# uTCA_Tongue3.net
KiCad netlist of a schematic drawn in Altium Designer
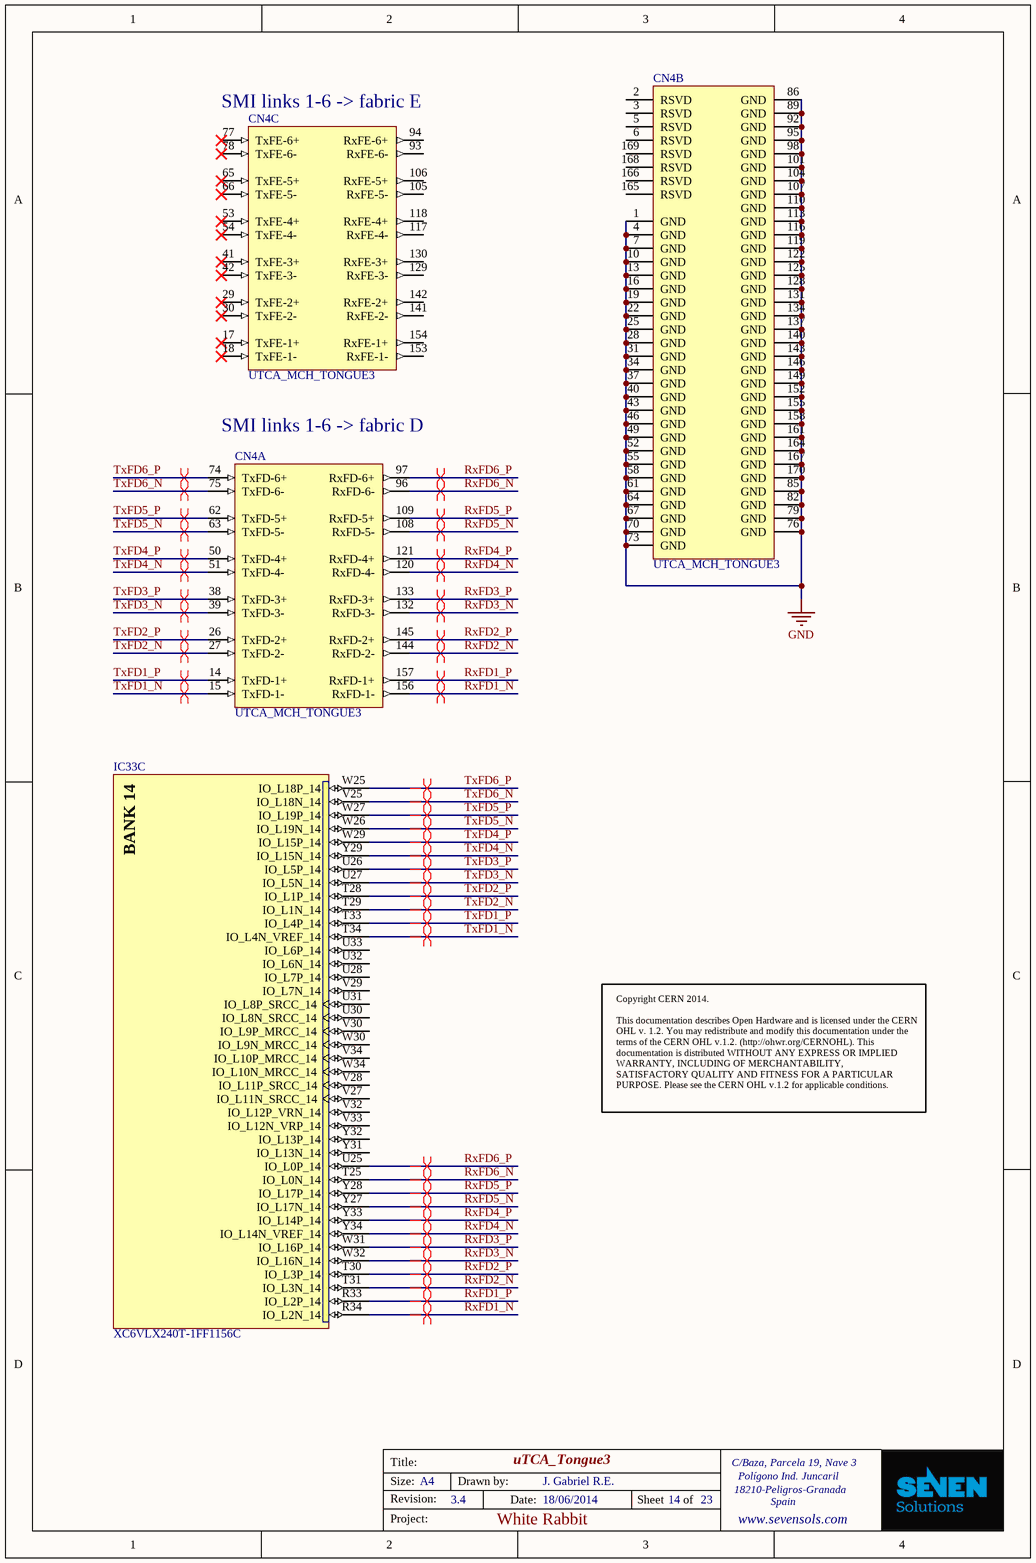
[diagram p0: uTCA_Tongue3.SchDoc]

(export (version "E")
  (design (tool "Eeschema 10.0.6"))
  (components
    (comp (ref "CN4")
      (value "UTCA_MCH_TONGUE3")
      (footprint "UTCA_MCH_TONGUE2_3_4")
      (description "microTCA MTCA.0 standard MCH connector 3")
      (libsource (lib "wr_switch") (part "UTCA_MCH_TONGUE3"))
    )
    (comp (ref "IC33")
      (value "XC6VLX240T-1FF1156C")
      (footprint "FF1156")
      (fields (field (name "PUBLISHER") "Altium Limited"))
      (libsource (lib "Xilinx Virtex-6") (part "XC6VLX240T-1FF1156C"))
    )
  )
  (nets
    (net (code "1") (name "/RxFD1_N") (class "Default")
      (node (ref "CN4") (pin "156") (pinfunction "RxFD-1-_156") (pintype "output"))
      (node (ref "IC33") (pin "R34") (pinfunction "IO_L2N_14_R34") (pintype "bidirectional"))
    )
    (net (code "2") (name "/RxFD1_P") (class "Default")
      (node (ref "CN4") (pin "157") (pinfunction "RxFD-1+_157") (pintype "output"))
      (node (ref "IC33") (pin "R33") (pinfunction "IO_L2P_14_R33") (pintype "bidirectional"))
    )
    (net (code "3") (name "/RxFD2_N") (class "Default")
      (node (ref "CN4") (pin "144") (pinfunction "RxFD-2-_144") (pintype "output"))
      (node (ref "IC33") (pin "T31") (pinfunction "IO_L3N_14_T31") (pintype "bidirectional"))
    )
    (net (code "4") (name "/RxFD2_P") (class "Default")
      (node (ref "CN4") (pin "145") (pinfunction "RxFD-2+_145") (pintype "output"))
      (node (ref "IC33") (pin "T30") (pinfunction "IO_L3P_14_T30") (pintype "bidirectional"))
    )
    (net (code "5") (name "/RxFD3_N") (class "Default")
      (node (ref "CN4") (pin "132") (pinfunction "RxFD-3-_132") (pintype "output"))
      (node (ref "IC33") (pin "W32") (pinfunction "IO_L16N_14_W32") (pintype "bidirectional"))
    )
    (net (code "6") (name "/RxFD3_P") (class "Default")
      (node (ref "CN4") (pin "133") (pinfunction "RxFD-3+_133") (pintype "output"))
      (node (ref "IC33") (pin "W31") (pinfunction "IO_L16P_14_W31") (pintype "bidirectional"))
    )
    (net (code "7") (name "/RxFD4_N") (class "Default")
      (node (ref "CN4") (pin "120") (pinfunction "RxFD-4-_120") (pintype "output"))
      (node (ref "IC33") (pin "Y34") (pinfunction "IO_L14N_VREF_14_Y34") (pintype "bidirectional"))
    )
    (net (code "8") (name "/RxFD4_P") (class "Default")
      (node (ref "CN4") (pin "121") (pinfunction "RxFD-4+_121") (pintype "output"))
      (node (ref "IC33") (pin "Y33") (pinfunction "IO_L14P_14_Y33") (pintype "bidirectional"))
    )
    (net (code "9") (name "/RxFD5_N") (class "Default")
      (node (ref "CN4") (pin "108") (pinfunction "RxFD-5-_108") (pintype "output"))
      (node (ref "IC33") (pin "Y27") (pinfunction "IO_L17N_14_Y27") (pintype "bidirectional"))
    )
    (net (code "10") (name "/RxFD5_P") (class "Default")
      (node (ref "CN4") (pin "109") (pinfunction "RxFD-5+_109") (pintype "output"))
      (node (ref "IC33") (pin "Y28") (pinfunction "IO_L17P_14_Y28") (pintype "bidirectional"))
    )
    (net (code "11") (name "/RxFD6_N") (class "Default")
      (node (ref "CN4") (pin "96") (pinfunction "RxFD-6-_96") (pintype "output"))
      (node (ref "IC33") (pin "T25") (pinfunction "IO_L0N_14_T25") (pintype "bidirectional"))
    )
    (net (code "12") (name "/RxFD6_P") (class "Default")
      (node (ref "CN4") (pin "97") (pinfunction "RxFD-6+_97") (pintype "output"))
      (node (ref "IC33") (pin "U25") (pinfunction "IO_L0P_14_U25") (pintype "bidirectional"))
    )
    (net (code "13") (name "/TxFD1_N") (class "Default")
      (node (ref "CN4") (pin "15") (pinfunction "TxFD-1-_15") (pintype "input"))
      (node (ref "IC33") (pin "T34") (pinfunction "IO_L4N_VREF_14_T34") (pintype "bidirectional"))
    )
    (net (code "14") (name "/TxFD1_P") (class "Default")
      (node (ref "CN4") (pin "14") (pinfunction "TxFD-1+_14") (pintype "input"))
      (node (ref "IC33") (pin "T33") (pinfunction "IO_L4P_14_T33") (pintype "bidirectional"))
    )
    (net (code "15") (name "/TxFD2_N") (class "Default")
      (node (ref "CN4") (pin "27") (pinfunction "TxFD-2-_27") (pintype "input"))
      (node (ref "IC33") (pin "T29") (pinfunction "IO_L1N_14_T29") (pintype "bidirectional"))
    )
    (net (code "16") (name "/TxFD2_P") (class "Default")
      (node (ref "CN4") (pin "26") (pinfunction "TxFD-2+_26") (pintype "input"))
      (node (ref "IC33") (pin "T28") (pinfunction "IO_L1P_14_T28") (pintype "bidirectional"))
    )
    (net (code "17") (name "/TxFD3_N") (class "Default")
      (node (ref "CN4") (pin "39") (pinfunction "TxFD-3-_39") (pintype "input"))
      (node (ref "IC33") (pin "U27") (pinfunction "IO_L5N_14_U27") (pintype "bidirectional"))
    )
    (net (code "18") (name "/TxFD3_P") (class "Default")
      (node (ref "CN4") (pin "38") (pinfunction "TxFD-3+_38") (pintype "input"))
      (node (ref "IC33") (pin "U26") (pinfunction "IO_L5P_14_U26") (pintype "bidirectional"))
    )
    (net (code "19") (name "/TxFD4_N") (class "Default")
      (node (ref "CN4") (pin "51") (pinfunction "TxFD-4-_51") (pintype "input"))
      (node (ref "IC33") (pin "Y29") (pinfunction "IO_L15N_14_Y29") (pintype "bidirectional"))
    )
    (net (code "20") (name "/TxFD4_P") (class "Default")
      (node (ref "CN4") (pin "50") (pinfunction "TxFD-4+_50") (pintype "input"))
      (node (ref "IC33") (pin "W29") (pinfunction "IO_L15P_14_W29") (pintype "bidirectional"))
    )
    (net (code "21") (name "/TxFD5_N") (class "Default")
      (node (ref "CN4") (pin "63") (pinfunction "TxFD-5-_63") (pintype "input"))
      (node (ref "IC33") (pin "W26") (pinfunction "IO_L19N_14_W26") (pintype "bidirectional"))
    )
    (net (code "22") (name "/TxFD5_P") (class "Default")
      (node (ref "CN4") (pin "62") (pinfunction "TxFD-5+_62") (pintype "input"))
      (node (ref "IC33") (pin "W27") (pinfunction "IO_L19P_14_W27") (pintype "bidirectional"))
    )
    (net (code "23") (name "/TxFD6_N") (class "Default")
      (node (ref "CN4") (pin "75") (pinfunction "TxFD-6-_75") (pintype "input"))
      (node (ref "IC33") (pin "V25") (pinfunction "IO_L18N_14_V25") (pintype "bidirectional"))
    )
    (net (code "24") (name "/TxFD6_P") (class "Default")
      (node (ref "CN4") (pin "74") (pinfunction "TxFD-6+_74") (pintype "input"))
      (node (ref "IC33") (pin "W25") (pinfunction "IO_L18P_14_W25") (pintype "bidirectional"))
    )
    (net (code "25") (name "GND") (class "Default")
      (node (ref "CN4") (pin "1") (pinfunction "GND_1") (pintype "power_in"))
      (node (ref "CN4") (pin "10") (pinfunction "GND_10") (pintype "power_in"))
      (node (ref "CN4") (pin "101") (pinfunction "GND_101") (pintype "power_in"))
      (node (ref "CN4") (pin "104") (pinfunction "GND_104") (pintype "power_in"))
      (node (ref "CN4") (pin "107") (pinfunction "GND_107") (pintype "power_in"))
      (node (ref "CN4") (pin "110") (pinfunction "GND_110") (pintype "power_in"))
      (node (ref "CN4") (pin "113") (pinfunction "GND_113") (pintype "power_in"))
      (node (ref "CN4") (pin "116") (pinfunction "GND_116") (pintype "power_in"))
      (node (ref "CN4") (pin "119") (pinfunction "GND_119") (pintype "power_in"))
      (node (ref "CN4") (pin "122") (pinfunction "GND_122") (pintype "power_in"))
      (node (ref "CN4") (pin "125") (pinfunction "GND_125") (pintype "power_in"))
      (node (ref "CN4") (pin "128") (pinfunction "GND_128") (pintype "power_in"))
      (node (ref "CN4") (pin "13") (pinfunction "GND_13") (pintype "power_in"))
      (node (ref "CN4") (pin "131") (pinfunction "GND_131") (pintype "power_in"))
      (node (ref "CN4") (pin "134") (pinfunction "GND_134") (pintype "power_in"))
      (node (ref "CN4") (pin "137") (pinfunction "GND_137") (pintype "power_in"))
      (node (ref "CN4") (pin "140") (pinfunction "GND_140") (pintype "power_in"))
      (node (ref "CN4") (pin "143") (pinfunction "GND_143") (pintype "power_in"))
      (node (ref "CN4") (pin "146") (pinfunction "GND_146") (pintype "power_in"))
      (node (ref "CN4") (pin "149") (pinfunction "GND_149") (pintype "power_in"))
      (node (ref "CN4") (pin "152") (pinfunction "GND_152") (pintype "power_in"))
      (node (ref "CN4") (pin "155") (pinfunction "GND_155") (pintype "power_in"))
      (node (ref "CN4") (pin "158") (pinfunction "GND_158") (pintype "power_in"))
      (node (ref "CN4") (pin "16") (pinfunction "GND_16") (pintype "power_in"))
      (node (ref "CN4") (pin "161") (pinfunction "GND_161") (pintype "power_in"))
      (node (ref "CN4") (pin "164") (pinfunction "GND_164") (pintype "power_in"))
      (node (ref "CN4") (pin "167") (pinfunction "GND_167") (pintype "power_in"))
      (node (ref "CN4") (pin "170") (pinfunction "GND_170") (pintype "power_in"))
      (node (ref "CN4") (pin "19") (pinfunction "GND_19") (pintype "power_in"))
      (node (ref "CN4") (pin "22") (pinfunction "GND_22") (pintype "power_in"))
      (node (ref "CN4") (pin "25") (pinfunction "GND_25") (pintype "power_in"))
      (node (ref "CN4") (pin "28") (pinfunction "GND_28") (pintype "power_in"))
      (node (ref "CN4") (pin "31") (pinfunction "GND_31") (pintype "power_in"))
      (node (ref "CN4") (pin "34") (pinfunction "GND_34") (pintype "power_in"))
      (node (ref "CN4") (pin "37") (pinfunction "GND_37") (pintype "power_in"))
      (node (ref "CN4") (pin "4") (pinfunction "GND_4") (pintype "power_in"))
      (node (ref "CN4") (pin "40") (pinfunction "GND_40") (pintype "power_in"))
      (node (ref "CN4") (pin "43") (pinfunction "GND_43") (pintype "power_in"))
      (node (ref "CN4") (pin "46") (pinfunction "GND_46") (pintype "power_in"))
      (node (ref "CN4") (pin "49") (pinfunction "GND_49") (pintype "power_in"))
      (node (ref "CN4") (pin "52") (pinfunction "GND_52") (pintype "power_in"))
      (node (ref "CN4") (pin "55") (pinfunction "GND_55") (pintype "power_in"))
      (node (ref "CN4") (pin "58") (pinfunction "GND_58") (pintype "power_in"))
      (node (ref "CN4") (pin "61") (pinfunction "GND_61") (pintype "power_in"))
      (node (ref "CN4") (pin "64") (pinfunction "GND_64") (pintype "power_in"))
      (node (ref "CN4") (pin "67") (pinfunction "GND_67") (pintype "power_in"))
      (node (ref "CN4") (pin "7") (pinfunction "GND_7") (pintype "power_in"))
      (node (ref "CN4") (pin "70") (pinfunction "GND_70") (pintype "power_in"))
      (node (ref "CN4") (pin "73") (pinfunction "GND_73") (pintype "power_in"))
      (node (ref "CN4") (pin "76") (pinfunction "GND_76") (pintype "power_in"))
      (node (ref "CN4") (pin "79") (pinfunction "GND_79") (pintype "power_in"))
      (node (ref "CN4") (pin "82") (pinfunction "GND_82") (pintype "power_in"))
      (node (ref "CN4") (pin "85") (pinfunction "GND_85") (pintype "power_in"))
      (node (ref "CN4") (pin "86") (pinfunction "GND_86") (pintype "power_in"))
      (node (ref "CN4") (pin "89") (pinfunction "GND_89") (pintype "power_in"))
      (node (ref "CN4") (pin "92") (pinfunction "GND_92") (pintype "power_in"))
      (node (ref "CN4") (pin "95") (pinfunction "GND_95") (pintype "power_in"))
      (node (ref "CN4") (pin "98") (pinfunction "GND_98") (pintype "power_in"))
    )
    (net (code "26") (name "unconnected-(CN4B-RSVD-Pad2)") (class "Default")
      (node (ref "CN4") (pin "2") (pinfunction "RSVD_2") (pintype "passive"))
    )
    (net (code "27") (name "unconnected-(CN4B-RSVD-Pad3)") (class "Default")
      (node (ref "CN4") (pin "3") (pinfunction "RSVD_3") (pintype "passive"))
    )
    (net (code "28") (name "unconnected-(CN4B-RSVD-Pad5)") (class "Default")
      (node (ref "CN4") (pin "5") (pinfunction "RSVD_5") (pintype "passive"))
    )
    (net (code "29") (name "unconnected-(CN4B-RSVD-Pad6)") (class "Default")
      (node (ref "CN4") (pin "6") (pinfunction "RSVD_6") (pintype "passive"))
    )
    (net (code "30") (name "unconnected-(CN4B-RSVD-Pad165)") (class "Default")
      (node (ref "CN4") (pin "165") (pinfunction "RSVD_165") (pintype "passive"))
    )
    (net (code "31") (name "unconnected-(CN4B-RSVD-Pad166)") (class "Default")
      (node (ref "CN4") (pin "166") (pinfunction "RSVD_166") (pintype "passive"))
    )
    (net (code "32") (name "unconnected-(CN4B-RSVD-Pad168)") (class "Default")
      (node (ref "CN4") (pin "168") (pinfunction "RSVD_168") (pintype "passive"))
    )
    (net (code "33") (name "unconnected-(CN4B-RSVD-Pad169)") (class "Default")
      (node (ref "CN4") (pin "169") (pinfunction "RSVD_169") (pintype "passive"))
    )
    (net (code "34") (name "unconnected-(CN4C-RxFE-1+-Pad154)") (class "Default")
      (node (ref "CN4") (pin "154") (pinfunction "RxFE-1+_154") (pintype "output"))
    )
    (net (code "35") (name "unconnected-(CN4C-RxFE-1--Pad153)") (class "Default")
      (node (ref "CN4") (pin "153") (pinfunction "RxFE-1-_153") (pintype "output"))
    )
    (net (code "36") (name "unconnected-(CN4C-RxFE-2+-Pad142)") (class "Default")
      (node (ref "CN4") (pin "142") (pinfunction "RxFE-2+_142") (pintype "output"))
    )
    (net (code "37") (name "unconnected-(CN4C-RxFE-2--Pad141)") (class "Default")
      (node (ref "CN4") (pin "141") (pinfunction "RxFE-2-_141") (pintype "output"))
    )
    (net (code "38") (name "unconnected-(CN4C-RxFE-3+-Pad130)") (class "Default")
      (node (ref "CN4") (pin "130") (pinfunction "RxFE-3+_130") (pintype "output"))
    )
    (net (code "39") (name "unconnected-(CN4C-RxFE-3--Pad129)") (class "Default")
      (node (ref "CN4") (pin "129") (pinfunction "RxFE-3-_129") (pintype "output"))
    )
    (net (code "40") (name "unconnected-(CN4C-RxFE-4+-Pad118)") (class "Default")
      (node (ref "CN4") (pin "118") (pinfunction "RxFE-4+_118") (pintype "output"))
    )
    (net (code "41") (name "unconnected-(CN4C-RxFE-4--Pad117)") (class "Default")
      (node (ref "CN4") (pin "117") (pinfunction "RxFE-4-_117") (pintype "output"))
    )
    (net (code "42") (name "unconnected-(CN4C-RxFE-5+-Pad106)") (class "Default")
      (node (ref "CN4") (pin "106") (pinfunction "RxFE-5+_106") (pintype "output"))
    )
    (net (code "43") (name "unconnected-(CN4C-RxFE-5--Pad105)") (class "Default")
      (node (ref "CN4") (pin "105") (pinfunction "RxFE-5-_105") (pintype "output"))
    )
    (net (code "44") (name "unconnected-(CN4C-RxFE-6+-Pad94)") (class "Default")
      (node (ref "CN4") (pin "94") (pinfunction "RxFE-6+_94") (pintype "output"))
    )
    (net (code "45") (name "unconnected-(CN4C-RxFE-6--Pad93)") (class "Default")
      (node (ref "CN4") (pin "93") (pinfunction "RxFE-6-_93") (pintype "output"))
    )
    (net (code "46") (name "unconnected-(CN4C-TxFE-1+-Pad17)") (class "Default")
      (node (ref "CN4") (pin "17") (pinfunction "TxFE-1+_17") (pintype "input+no_connect"))
    )
    (net (code "47") (name "unconnected-(CN4C-TxFE-1--Pad18)") (class "Default")
      (node (ref "CN4") (pin "18") (pinfunction "TxFE-1-_18") (pintype "input+no_connect"))
    )
    (net (code "48") (name "unconnected-(CN4C-TxFE-2+-Pad29)") (class "Default")
      (node (ref "CN4") (pin "29") (pinfunction "TxFE-2+_29") (pintype "input+no_connect"))
    )
    (net (code "49") (name "unconnected-(CN4C-TxFE-2--Pad30)") (class "Default")
      (node (ref "CN4") (pin "30") (pinfunction "TxFE-2-_30") (pintype "input+no_connect"))
    )
    (net (code "50") (name "unconnected-(CN4C-TxFE-3+-Pad41)") (class "Default")
      (node (ref "CN4") (pin "41") (pinfunction "TxFE-3+_41") (pintype "input+no_connect"))
    )
    (net (code "51") (name "unconnected-(CN4C-TxFE-3--Pad42)") (class "Default")
      (node (ref "CN4") (pin "42") (pinfunction "TxFE-3-_42") (pintype "input+no_connect"))
    )
    (net (code "52") (name "unconnected-(CN4C-TxFE-4+-Pad53)") (class "Default")
      (node (ref "CN4") (pin "53") (pinfunction "TxFE-4+_53") (pintype "input+no_connect"))
    )
    (net (code "53") (name "unconnected-(CN4C-TxFE-4--Pad54)") (class "Default")
      (node (ref "CN4") (pin "54") (pinfunction "TxFE-4-_54") (pintype "input+no_connect"))
    )
    (net (code "54") (name "unconnected-(CN4C-TxFE-5+-Pad65)") (class "Default")
      (node (ref "CN4") (pin "65") (pinfunction "TxFE-5+_65") (pintype "input+no_connect"))
    )
    (net (code "55") (name "unconnected-(CN4C-TxFE-5--Pad66)") (class "Default")
      (node (ref "CN4") (pin "66") (pinfunction "TxFE-5-_66") (pintype "input+no_connect"))
    )
    (net (code "56") (name "unconnected-(CN4C-TxFE-6+-Pad77)") (class "Default")
      (node (ref "CN4") (pin "77") (pinfunction "TxFE-6+_77") (pintype "input+no_connect"))
    )
    (net (code "57") (name "unconnected-(CN4C-TxFE-6--Pad78)") (class "Default")
      (node (ref "CN4") (pin "78") (pinfunction "TxFE-6-_78") (pintype "input+no_connect"))
    )
    (net (code "58") (name "unconnected-(IC33C-IO_L6N_14-PadU32)") (class "Default")
      (node (ref "IC33") (pin "U32") (pinfunction "IO_L6N_14_U32") (pintype "bidirectional"))
    )
    (net (code "59") (name "unconnected-(IC33C-IO_L6P_14-PadU33)") (class "Default")
      (node (ref "IC33") (pin "U33") (pinfunction "IO_L6P_14_U33") (pintype "bidirectional"))
    )
    (net (code "60") (name "unconnected-(IC33C-IO_L7N_14-PadV29)") (class "Default")
      (node (ref "IC33") (pin "V29") (pinfunction "IO_L7N_14_V29") (pintype "bidirectional"))
    )
    (net (code "61") (name "unconnected-(IC33C-IO_L7P_14-PadU28)") (class "Default")
      (node (ref "IC33") (pin "U28") (pinfunction "IO_L7P_14_U28") (pintype "bidirectional"))
    )
    (net (code "62") (name "unconnected-(IC33C-IO_L8N_SRCC_14-PadU30)") (class "Default")
      (node (ref "IC33") (pin "U30") (pinfunction "IO_L8N_SRCC_14_U30") (pintype "bidirectional"))
    )
    (net (code "63") (name "unconnected-(IC33C-IO_L8P_SRCC_14-PadU31)") (class "Default")
      (node (ref "IC33") (pin "U31") (pinfunction "IO_L8P_SRCC_14_U31") (pintype "bidirectional"))
    )
    (net (code "64") (name "unconnected-(IC33C-IO_L9N_MRCC_14-PadW30)") (class "Default")
      (node (ref "IC33") (pin "W30") (pinfunction "IO_L9N_MRCC_14_W30") (pintype "bidirectional"))
    )
    (net (code "65") (name "unconnected-(IC33C-IO_L9P_MRCC_14-PadV30)") (class "Default")
      (node (ref "IC33") (pin "V30") (pinfunction "IO_L9P_MRCC_14_V30") (pintype "bidirectional"))
    )
    (net (code "66") (name "unconnected-(IC33C-IO_L10N_MRCC_14-PadW34)") (class "Default")
      (node (ref "IC33") (pin "W34") (pinfunction "IO_L10N_MRCC_14_W34") (pintype "bidirectional"))
    )
    (net (code "67") (name "unconnected-(IC33C-IO_L10P_MRCC_14-PadV34)") (class "Default")
      (node (ref "IC33") (pin "V34") (pinfunction "IO_L10P_MRCC_14_V34") (pintype "bidirectional"))
    )
    (net (code "68") (name "unconnected-(IC33C-IO_L11N_SRCC_14-PadV27)") (class "Default")
      (node (ref "IC33") (pin "V27") (pinfunction "IO_L11N_SRCC_14_V27") (pintype "bidirectional"))
    )
    (net (code "69") (name "unconnected-(IC33C-IO_L11P_SRCC_14-PadV28)") (class "Default")
      (node (ref "IC33") (pin "V28") (pinfunction "IO_L11P_SRCC_14_V28") (pintype "bidirectional"))
    )
    (net (code "70") (name "unconnected-(IC33C-IO_L12N_VRP_14-PadV33)") (class "Default")
      (node (ref "IC33") (pin "V33") (pinfunction "IO_L12N_VRP_14_V33") (pintype "bidirectional"))
    )
    (net (code "71") (name "unconnected-(IC33C-IO_L12P_VRN_14-PadV32)") (class "Default")
      (node (ref "IC33") (pin "V32") (pinfunction "IO_L12P_VRN_14_V32") (pintype "bidirectional"))
    )
    (net (code "72") (name "unconnected-(IC33C-IO_L13N_14-PadY31)") (class "Default")
      (node (ref "IC33") (pin "Y31") (pinfunction "IO_L13N_14_Y31") (pintype "bidirectional"))
    )
    (net (code "73") (name "unconnected-(IC33C-IO_L13P_14-PadY32)") (class "Default")
      (node (ref "IC33") (pin "Y32") (pinfunction "IO_L13P_14_Y32") (pintype "bidirectional"))
    )
  )
)
